# Fonte.net
KiCad netlist of a schematic drawn in Altium Designer
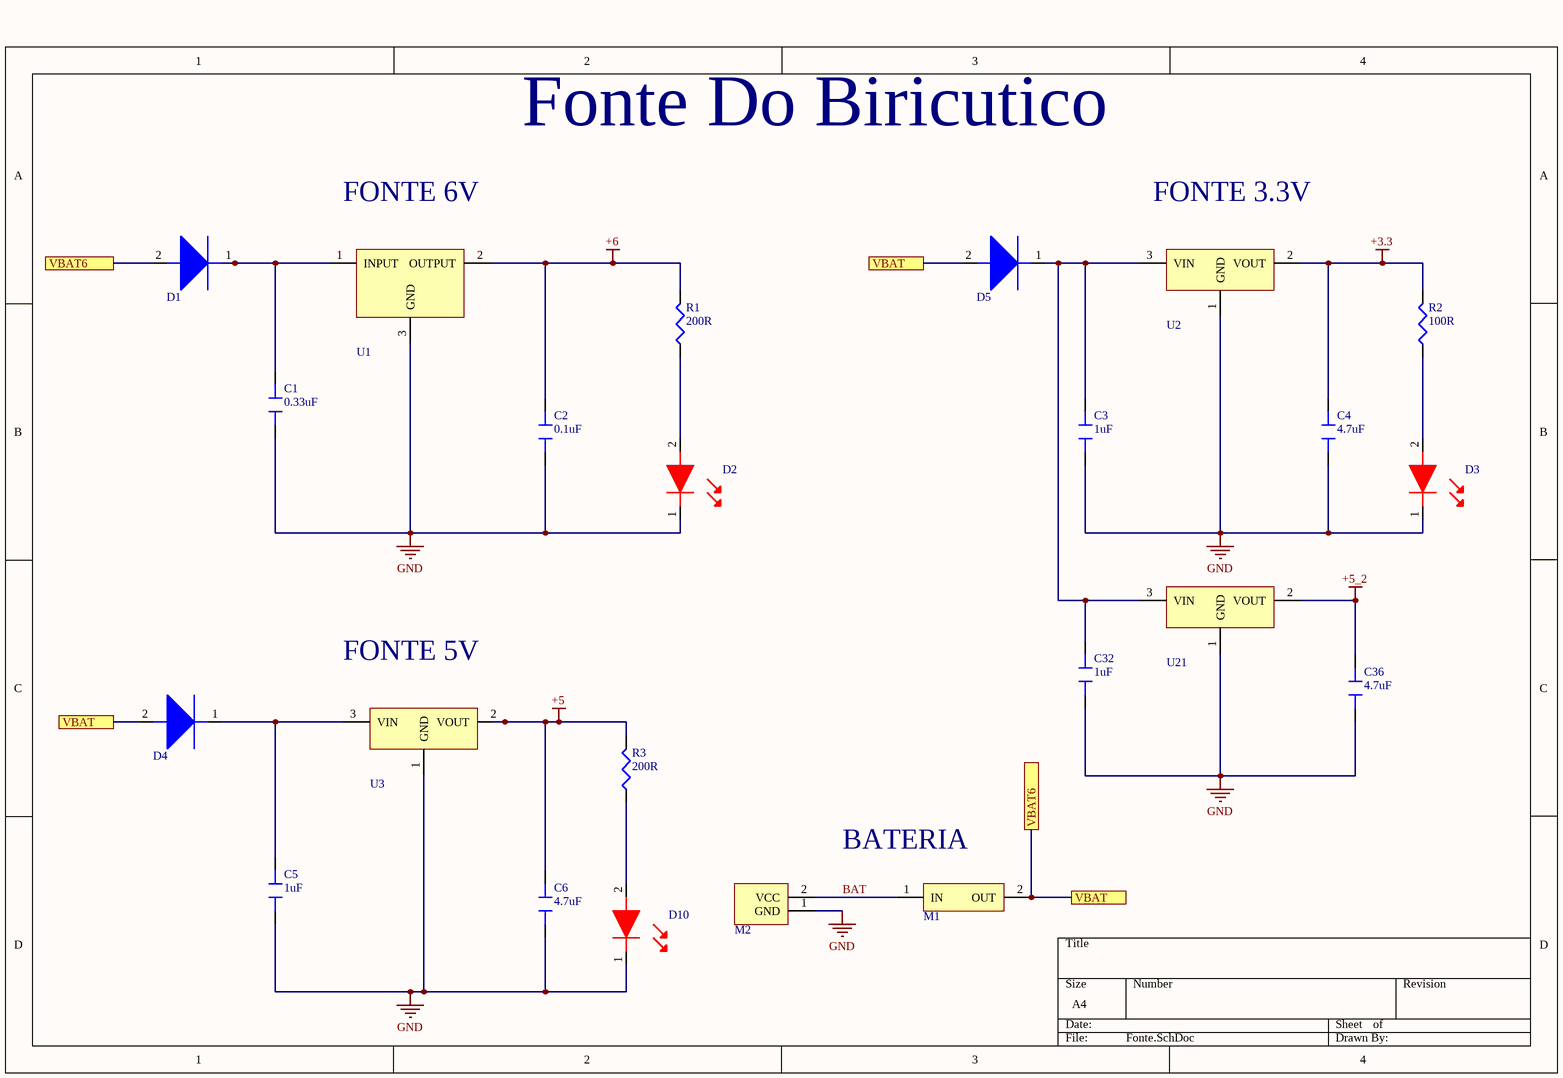
[diagram p0: Fonte.SchDoc]

(export (version "E")
  (design (tool "Eeschema 10.0.6"))
  (components
    (comp (ref "C1")
      (value "0.33uF")
      (footprint "CAPACITOR 0805")
      (description "Multilayer Ceramic Capacitors MLCC - SMD/SMT 0805 0.33uF 16volts X7R 5%")
      (fields
        (field (name "MANUFACTURER") "Vishay Vitramon")
        (field (name "MANUFACTURER PART NUMBER") "VJ0805Y334JXJRW1BC")
      )
      (libsource (lib "BiricuticoBonito") (part "Capacitor 0.33uF 0805"))
    )
    (comp (ref "C2")
      (value "0.1uF")
      (footprint "CAPACITOR 0805")
      (description "Multilayer Ceramic Capacitors MLCC - SMD/SMT .1uF 50volts 10%")
      (fields
        (field (name "MANUFACTURER") "Vishay Vitramon")
        (field (name "MANUFACTURER PART NUMBER") "VJ0805Y104KXAAT")
      )
      (libsource (lib "BiricuticoBonito") (part "Capacitor  0.1uF 0805"))
    )
    (comp (ref "C3")
      (value "1uF")
      (footprint "CAPACITOR 0805")
      (description "Cap Ceramic 1uF 25V X7R 10% SMD 0805 125C Blister T/R")
      (fields
        (field (name "MANUFACTURER") "Vishay")
        (field (name "MANUFACTURER PART NUMBER") "VJ0805Y105KXXTW1BC")
      )
      (libsource (lib "BiricuticoBonito") (part "Capacitor 1uF 0805"))
    )
    (comp (ref "C4")
      (value "4.7uF")
      (footprint "CAPACITOR 0805")
      (description "MURATA - GRM21BR61H475KE51L - CAP, 4.7µF, 50V, 10%, X5R, 0805")
      (fields
        (field (name "MANUFACTURER") "Murata")
        (field (name "MANUFACTURER PART NUMBER") "GRM21BR61H475KE51L")
      )
      (libsource (lib "BiricuticoBonito") (part "Capacitor 4.7uF 0805"))
    )
    (comp (ref "C5")
      (value "1uF")
      (footprint "CAPACITOR 0805")
      (description "Cap Ceramic 1uF 25V X7R 10% SMD 0805 125C Blister T/R")
      (fields
        (field (name "MANUFACTURER") "Vishay")
        (field (name "MANUFACTURER PART NUMBER") "VJ0805Y105KXXTW1BC")
      )
      (libsource (lib "BiricuticoBonito") (part "Capacitor 1uF 0805"))
    )
    (comp (ref "C6")
      (value "4.7uF")
      (footprint "CAPACITOR 0805")
      (description "MURATA - GRM21BR61H475KE51L - CAP, 4.7µF, 50V, 10%, X5R, 0805")
      (fields
        (field (name "MANUFACTURER") "Murata")
        (field (name "MANUFACTURER PART NUMBER") "GRM21BR61H475KE51L")
      )
      (libsource (lib "BiricuticoBonito") (part "Capacitor 4.7uF 0805"))
    )
    (comp (ref "C32")
      (value "1uF")
      (footprint "CAPACITOR 0805")
      (description "Cap Ceramic 1uF 25V X7R 10% SMD 0805 125C Blister T/R")
      (fields
        (field (name "MANUFACTURER") "Vishay")
        (field (name "MANUFACTURER PART NUMBER") "VJ0805Y105KXXTW1BC")
      )
      (libsource (lib "BiricuticoBonito") (part "Capacitor 1uF 0805"))
    )
    (comp (ref "C36")
      (value "4.7uF")
      (footprint "CAPACITOR 0805")
      (description "MURATA - GRM21BR61H475KE51L - CAP, 4.7µF, 50V, 10%, X5R, 0805")
      (fields
        (field (name "MANUFACTURER") "Murata")
        (field (name "MANUFACTURER PART NUMBER") "GRM21BR61H475KE51L")
      )
      (libsource (lib "BiricuticoBonito") (part "Capacitor 4.7uF 0805"))
    )
    (comp (ref "D1")
      (value "Schottky Diode")
      (footprint "SODFL3516X85N")
      (description "DIODE SCHOTTKY 40V 3A MINI2")
      (fields
        (field (name "MANUFACTURER") "Panasonic")
        (field (name "MANUFACTURER PART NUMBER") "DB2W40300L")
      )
      (libsource (lib "BiricuticoBonito") (part "Schottky Diode"))
    )
    (comp (ref "D2")
      (value "Standard LEDs - SMD")
      (footprint "Standard LEDs - SMD")
      (description "WURTH ELEKTRONIK - 150060RS75000 - LED, 0603, RED, 250MCD, 625NM")
      (fields
        (field (name "MANUFACTURER") "Wurth Electronics")
        (field (name "MANUFACTURER PART NUMBER") "150060RS75000")
      )
      (libsource (lib "BiricuticoBonito") (part "Standard LEDs - SMD"))
    )
    (comp (ref "D3")
      (value "Standard LEDs - SMD")
      (footprint "Standard LEDs - SMD")
      (description "WURTH ELEKTRONIK - 150060RS75000 - LED, 0603, RED, 250MCD, 625NM")
      (fields
        (field (name "MANUFACTURER") "Wurth Electronics")
        (field (name "MANUFACTURER PART NUMBER") "150060RS75000")
      )
      (libsource (lib "BiricuticoBonito") (part "Standard LEDs - SMD"))
    )
    (comp (ref "D4")
      (value "Schottky Diode")
      (footprint "SODFL3516X85N")
      (description "DIODE SCHOTTKY 40V 3A MINI2")
      (fields
        (field (name "MANUFACTURER") "Panasonic")
        (field (name "MANUFACTURER PART NUMBER") "DB2W40300L")
      )
      (libsource (lib "BiricuticoBonito") (part "Schottky Diode"))
    )
    (comp (ref "D5")
      (value "Schottky Diode")
      (footprint "SODFL3516X85N")
      (description "DIODE SCHOTTKY 40V 3A MINI2")
      (fields
        (field (name "MANUFACTURER") "Panasonic")
        (field (name "MANUFACTURER PART NUMBER") "DB2W40300L")
      )
      (libsource (lib "BiricuticoBonito") (part "Schottky Diode"))
    )
    (comp (ref "D10")
      (value "Standard LEDs - SMD")
      (footprint "Standard LEDs - SMD")
      (description "WURTH ELEKTRONIK - 150060RS75000 - LED, 0603, RED, 250MCD, 625NM")
      (fields
        (field (name "MANUFACTURER") "Wurth Electronics")
        (field (name "MANUFACTURER PART NUMBER") "150060RS75000")
      )
      (libsource (lib "BiricuticoBonito") (part "Standard LEDs - SMD"))
    )
    (comp (ref "M1")
      (value "Slide Switches")
      (footprint "Power_Switch")
      (description "46202LRX-")
      (fields
        (field (name "MANUFACTURER") "Switchcraft")
        (field (name "MANUFACTURER PART NUMBER") "46202LRX")
      )
      (libsource (lib "BiricuticoBonito") (part "Slide Switches"))
    )
    (comp (ref "M2")
      (value "Headers (1x2)")
      (footprint "BATT")
      (description "Headers & Wire Housings HDR STRT SINGLE 2P")
      (fields (field (name "MANUFACTURER") "Molex") (field (name "MANUFACTURER PART NUMBER") "90136-1202"))
      (libsource (lib "BiricuticoBonito") (part "Headers (1x2)"))
    )
    (comp (ref "R1")
      (value "200R")
      (footprint "6-0805_M")
      (description "RES SMD 200 OHM 1% 1/8W 0805")
      (fields
        (field (name "MANUFACTURER") "Vishay")
        (field (name "MANUFACTURER PART NUMBER") "CRCW0805200RFKEA")
      )
      (libsource (lib "BiricuticoBonito") (part "Resistor 200 0805"))
    )
    (comp (ref "R2")
      (value "100R")
      (footprint "0603")
      (description "RES SMD 100 OHM 1% 1/10W 0603")
      (fields
        (field (name "MANUFACTURER") "Vishay Intertechnology")
        (field (name "MANUFACTURER PART NUMBER") "CRCW0603100RFKEA")
      )
      (libsource (lib "BiricuticoBonito") (part "Resistor 100 0603"))
    )
    (comp (ref "R3")
      (value "200R")
      (footprint "6-0805_M")
      (description "RES SMD 200 OHM 1% 1/8W 0805")
      (fields
        (field (name "MANUFACTURER") "Vishay")
        (field (name "MANUFACTURER PART NUMBER") "CRCW0805200RFKEA")
      )
      (libsource (lib "BiricuticoBonito") (part "Resistor 200 0805"))
    )
    (comp (ref "U1")
      (value "Voltage Regulators 6V")
      (footprint "Voltage Regulators 6V")
      (description "IC REG LINEAR 6V 1.5A D2PAK")
      (fields
        (field (name "MANUFACTURER") "STMicroelectronics")
        (field (name "MANUFACTURER PART NUMBER") "L7806ABD2T-TR")
      )
      (libsource (lib "BiricuticoBonito") (part "Voltage Regulators 6V"))
    )
    (comp (ref "U2")
      (value "Voltage Regulators 3.3V")
      (footprint "SOT230P700X180-4N")
      (description "IC REG LINEAR 3.3V 1.2A SOT223")
      (fields
        (field (name "MANUFACTURER") "STMicroelectronics")
        (field (name "MANUFACTURER PART NUMBER") "LDL1117S33R")
      )
      (libsource (lib "BiricuticoBonito") (part "Voltage Regulators 3.3V"))
    )
    (comp (ref "U3")
      (value "Voltage Regulators 5V")
      (footprint "SOT230P700X180-4N")
      (description "IC REG LINEAR 5V 1.2A SOT223")
      (fields
        (field (name "MANUFACTURER") "STMicroelectronics")
        (field (name "MANUFACTURER PART NUMBER") "LDL1117S50R")
      )
      (libsource (lib "BiricuticoBonito") (part "Voltage Regulators 5V"))
    )
    (comp (ref "U21")
      (value "Voltage Regulators 5V")
      (footprint "SOT230P700X180-4N")
      (description "IC REG LINEAR 5V 1.2A SOT223")
      (fields
        (field (name "MANUFACTURER") "STMicroelectronics")
        (field (name "MANUFACTURER PART NUMBER") "LDL1117S50R")
      )
      (libsource (lib "BiricuticoBonito") (part "Voltage Regulators 5V"))
    )
  )
  (nets
    (net (code "1") (name "+3.3") (class "Default")
      (node (ref "C4") (pin "2") (pinfunction "34_2") (pintype "passive"))
      (node (ref "R2") (pin "2") (pinfunction "27_2") (pintype "passive"))
      (node (ref "U2") (pin "2") (pinfunction "VOUT_2") (pintype "passive"))
    )
    (net (code "2") (name "+5") (class "Default")
      (node (ref "C6") (pin "2") (pinfunction "34_2") (pintype "passive"))
      (node (ref "R3") (pin "2") (pinfunction "27_2") (pintype "passive"))
      (node (ref "U3") (pin "2") (pinfunction "VOUT_2") (pintype "passive"))
    )
    (net (code "3") (name "+5_2") (class "Default")
      (node (ref "C36") (pin "2") (pinfunction "34_2") (pintype "passive"))
      (node (ref "U21") (pin "2") (pinfunction "VOUT_2") (pintype "passive"))
    )
    (net (code "4") (name "+6") (class "Default")
      (node (ref "C2") (pin "1") (pinfunction "33_1") (pintype "passive"))
      (node (ref "R1") (pin "2") (pinfunction "27_2") (pintype "passive"))
      (node (ref "U1") (pin "2") (pinfunction "OUTPUT_2") (pintype "passive"))
    )
    (net (code "5") (name "/BAT") (class "Default")
      (node (ref "M1") (pin "1") (pinfunction "IN_1") (pintype "passive"))
      (node (ref "M2") (pin "2") (pinfunction "VCC_2") (pintype "passive"))
    )
    (net (code "6") (name "/VBAT") (class "Default")
      (node (ref "D1") (pin "2") (pinfunction "23_2") (pintype "passive"))
      (node (ref "D4") (pin "2") (pinfunction "23_2") (pintype "passive"))
      (node (ref "D5") (pin "2") (pinfunction "23_2") (pintype "passive"))
      (node (ref "M1") (pin "2") (pinfunction "OUT_2") (pintype "passive"))
    )
    (net (code "7") (name "GND") (class "Default")
      (node (ref "C1") (pin "1") (pinfunction "33_1") (pintype "passive"))
      (node (ref "C2") (pin "2") (pinfunction "34_2") (pintype "passive"))
      (node (ref "C3") (pin "1") (pinfunction "33_1") (pintype "passive"))
      (node (ref "C32") (pin "1") (pinfunction "33_1") (pintype "passive"))
      (node (ref "C36") (pin "1") (pinfunction "33_1") (pintype "passive"))
      (node (ref "C4") (pin "1") (pinfunction "33_1") (pintype "passive"))
      (node (ref "C5") (pin "1") (pinfunction "33_1") (pintype "passive"))
      (node (ref "C6") (pin "1") (pinfunction "33_1") (pintype "passive"))
      (node (ref "D10") (pin "1") (pinfunction "19_1") (pintype "passive"))
      (node (ref "D2") (pin "1") (pinfunction "19_1") (pintype "passive"))
      (node (ref "D3") (pin "1") (pinfunction "19_1") (pintype "passive"))
      (node (ref "M2") (pin "1") (pinfunction "GND_1") (pintype "passive"))
      (node (ref "U1") (pin "3") (pinfunction "GND_3") (pintype "passive"))
      (node (ref "U2") (pin "1") (pinfunction "GND_1") (pintype "passive"))
      (node (ref "U21") (pin "1") (pinfunction "GND_1") (pintype "passive"))
      (node (ref "U3") (pin "1") (pinfunction "GND_1") (pintype "passive"))
    )
    (net (code "8") (name "Net-(C1-34)") (class "Default")
      (node (ref "C1") (pin "2") (pinfunction "34_2") (pintype "passive"))
      (node (ref "D1") (pin "1") (pinfunction "22_1") (pintype "passive"))
      (node (ref "U1") (pin "1") (pinfunction "INPUT_1") (pintype "passive"))
    )
    (net (code "9") (name "Net-(C3-34)") (class "Default")
      (node (ref "C3") (pin "2") (pinfunction "34_2") (pintype "passive"))
      (node (ref "C32") (pin "2") (pinfunction "34_2") (pintype "passive"))
      (node (ref "D5") (pin "1") (pinfunction "22_1") (pintype "passive"))
      (node (ref "U2") (pin "3") (pinfunction "VIN_3") (pintype "passive"))
      (node (ref "U21") (pin "3") (pinfunction "VIN_3") (pintype "passive"))
    )
    (net (code "10") (name "Net-(C5-34)") (class "Default")
      (node (ref "C5") (pin "2") (pinfunction "34_2") (pintype "passive"))
      (node (ref "D4") (pin "1") (pinfunction "22_1") (pintype "passive"))
      (node (ref "U3") (pin "3") (pinfunction "VIN_3") (pintype "passive"))
    )
    (net (code "11") (name "Net-(D2-18)") (class "Default")
      (node (ref "D2") (pin "2") (pinfunction "18_2") (pintype "passive"))
      (node (ref "R1") (pin "1") (pinfunction "28_1") (pintype "passive"))
    )
    (net (code "12") (name "Net-(D3-18)") (class "Default")
      (node (ref "D3") (pin "2") (pinfunction "18_2") (pintype "passive"))
      (node (ref "R2") (pin "1") (pinfunction "28_1") (pintype "passive"))
    )
    (net (code "13") (name "Net-(D10-18)") (class "Default")
      (node (ref "D10") (pin "2") (pinfunction "18_2") (pintype "passive"))
      (node (ref "R3") (pin "1") (pinfunction "28_1") (pintype "passive"))
    )
  )
)
